# 7seg_unit_smd.net
KiCad netlist of a schematic drawn in EAGLE
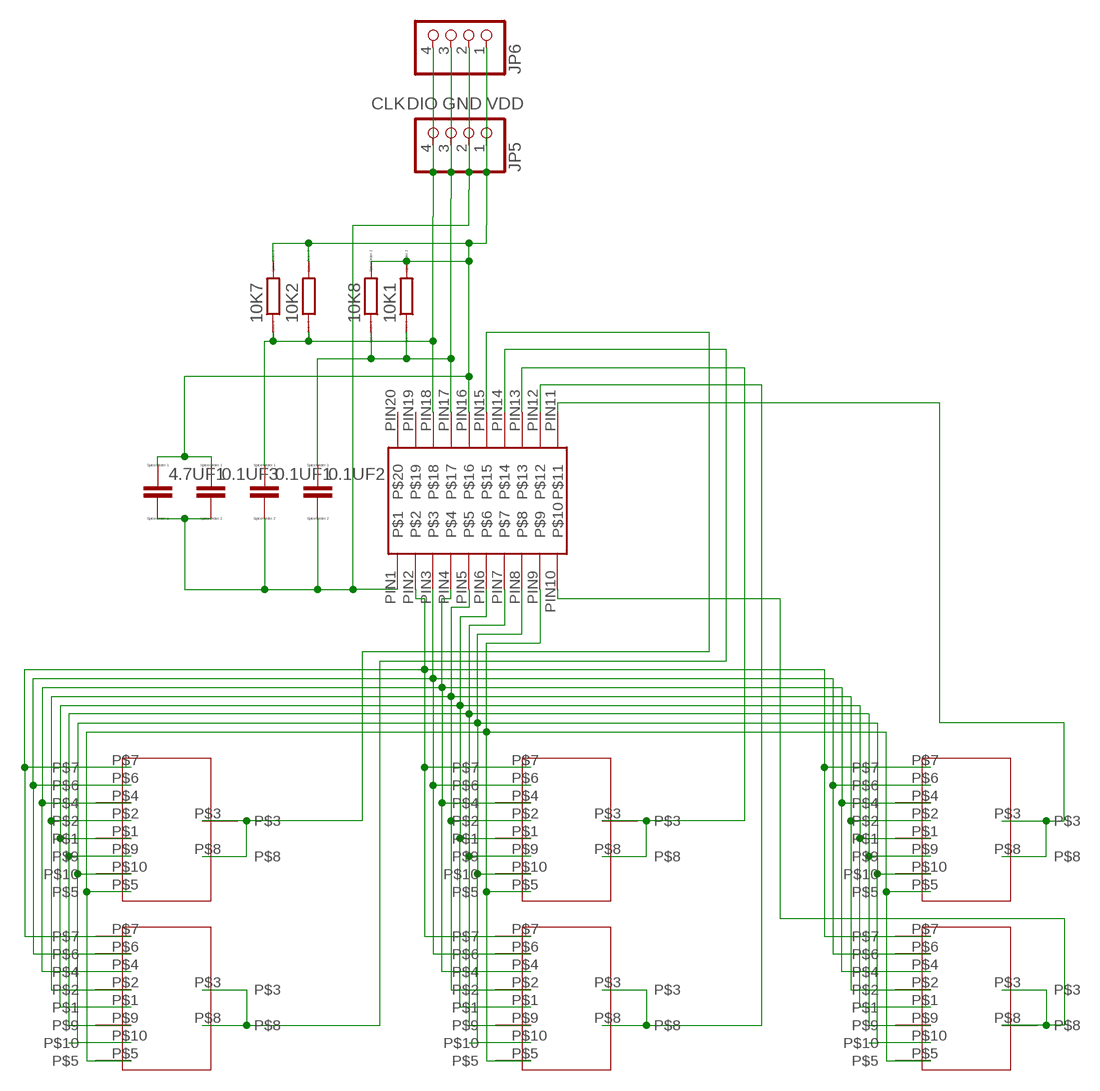
[diagram p0: schematic, sheet 1]

(export (version "E")
  (design (tool "Eeschema 10.0.6"))
  (components
    (comp (ref "0.1UF1")
      (value "CC1206")
      (footprint "eagle-import:C1206")
      (libsource (lib "eagle-import") (part "CC1206"))
    )
    (comp (ref "0.1UF2")
      (value "CC1206")
      (footprint "eagle-import:C1206")
      (libsource (lib "eagle-import") (part "CC1206"))
    )
    (comp (ref "0.1UF3")
      (value "CC1206")
      (footprint "eagle-import:C1206")
      (libsource (lib "eagle-import") (part "CC1206"))
    )
    (comp (ref "4.7UF1")
      (value "CC2012")
      (footprint "eagle-import:C2012")
      (libsource (lib "eagle-import") (part "CC2012"))
    )
    (comp (ref "7SEG_NEW1")
      (value "7SEG_NEW")
      (footprint "eagle-import:7SEG_NEW")
      (libsource (lib "eagle-import") (part "7SEG_NEW"))
    )
    (comp (ref "7SEG_NEW2")
      (value "7SEG_NEW")
      (footprint "eagle-import:7SEG_NEW")
      (libsource (lib "eagle-import") (part "7SEG_NEW"))
    )
    (comp (ref "7SEG_NEW3")
      (value "7SEG_NEW")
      (footprint "eagle-import:7SEG_NEW")
      (libsource (lib "eagle-import") (part "7SEG_NEW"))
    )
    (comp (ref "7SEG_NEW4")
      (value "7SEG_NEW")
      (footprint "eagle-import:7SEG_NEW")
      (libsource (lib "eagle-import") (part "7SEG_NEW"))
    )
    (comp (ref "7SEG_NEW5")
      (value "7SEG_NEW")
      (footprint "eagle-import:7SEG_NEW")
      (libsource (lib "eagle-import") (part "7SEG_NEW"))
    )
    (comp (ref "7SEG_NEW6")
      (value "7SEG_NEW")
      (footprint "eagle-import:7SEG_NEW")
      (libsource (lib "eagle-import") (part "7SEG_NEW"))
    )
    (comp (ref "10K1")
      (value "RR1206")
      (footprint "eagle-import:R1206")
      (libsource (lib "eagle-import") (part "RR1206"))
    )
    (comp (ref "10K2")
      (value "RR1206")
      (footprint "eagle-import:R1206")
      (libsource (lib "eagle-import") (part "RR1206"))
    )
    (comp (ref "10K7")
      (value "RR1206")
      (footprint "eagle-import:R1206")
      (libsource (lib "eagle-import") (part "RR1206"))
    )
    (comp (ref "10K8")
      (value "RR1206")
      (footprint "eagle-import:R1206")
      (libsource (lib "eagle-import") (part "RR1206"))
    )
    (comp (ref "JP5")
      (value "PINHD-1X4")
      (footprint "eagle-import:1X04")
      (libsource (lib "eagle-import") (part "PINHD-1X4"))
    )
    (comp (ref "JP6")
      (value "PINHD-1X4")
      (footprint "eagle-import:1X04")
      (libsource (lib "eagle-import") (part "PINHD-1X4"))
    )
    (comp (ref "TM1637-SMD1")
      (value "TM1637")
      (footprint "eagle-import:TM1637")
      (libsource (lib "eagle-import") (part "TM1637"))
    )
  )
  (nets
    (net (code "1") (name "/CLK") (class "Default")
      (node (ref "0.1UF1") (pin "1") (pinfunction "1_1") (pintype "passive"))
      (node (ref "10K2") (pin "1") (pinfunction "1_1") (pintype "passive"))
      (node (ref "10K7") (pin "1") (pinfunction "1_1") (pintype "passive"))
      (node (ref "JP5") (pin "4") (pinfunction "4_4") (pintype "passive"))
      (node (ref "JP6") (pin "4") (pinfunction "4_4") (pintype "passive"))
      (node (ref "TM1637-SMD1") (pin "PIN18") (pinfunction "P$18_PIN18") (pintype "bidirectional"))
    )
    (net (code "2") (name "/DIO") (class "Default")
      (node (ref "0.1UF2") (pin "1") (pinfunction "1_1") (pintype "passive"))
      (node (ref "10K1") (pin "1") (pinfunction "1_1") (pintype "passive"))
      (node (ref "10K8") (pin "1") (pinfunction "1_1") (pintype "passive"))
      (node (ref "JP5") (pin "3") (pinfunction "3_3") (pintype "passive"))
      (node (ref "JP6") (pin "3") (pinfunction "3_3") (pintype "passive"))
      (node (ref "TM1637-SMD1") (pin "PIN17") (pinfunction "P$17_PIN17") (pintype "bidirectional"))
    )
    (net (code "3") (name "/GND") (class "Default")
      (node (ref "0.1UF1") (pin "2") (pinfunction "2_2") (pintype "passive"))
      (node (ref "0.1UF2") (pin "2") (pinfunction "2_2") (pintype "passive"))
      (node (ref "0.1UF3") (pin "2") (pinfunction "2_2") (pintype "passive"))
      (node (ref "4.7UF1") (pin "2") (pinfunction "2_2") (pintype "passive"))
      (node (ref "JP5") (pin "2") (pinfunction "2_2") (pintype "passive"))
      (node (ref "JP6") (pin "2") (pinfunction "2_2") (pintype "passive"))
      (node (ref "TM1637-SMD1") (pin "PIN1") (pinfunction "P$1_PIN1") (pintype "bidirectional"))
    )
    (net (code "4") (name "/VDD") (class "Default")
      (node (ref "0.1UF3") (pin "1") (pinfunction "1_1") (pintype "passive"))
      (node (ref "10K1") (pin "2") (pinfunction "2_2") (pintype "passive"))
      (node (ref "10K2") (pin "2") (pinfunction "2_2") (pintype "passive"))
      (node (ref "10K7") (pin "2") (pinfunction "2_2") (pintype "passive"))
      (node (ref "10K8") (pin "2") (pinfunction "2_2") (pintype "passive"))
      (node (ref "4.7UF1") (pin "1") (pinfunction "1_1") (pintype "passive"))
      (node (ref "JP5") (pin "1") (pinfunction "1_1") (pintype "passive"))
      (node (ref "JP6") (pin "1") (pinfunction "1_1") (pintype "passive"))
      (node (ref "TM1637-SMD1") (pin "PIN16") (pinfunction "P$16_PIN16") (pintype "bidirectional"))
    )
    (net (code "5") (name "Net-(TM1637-SMD1-P$2)") (class "Default")
      (node (ref "7SEG_NEW1") (pin "P$7") (pinfunction "P$7_P$7") (pintype "bidirectional"))
      (node (ref "7SEG_NEW2") (pin "P$7") (pinfunction "P$7_P$7") (pintype "bidirectional"))
      (node (ref "7SEG_NEW3") (pin "P$7") (pinfunction "P$7_P$7") (pintype "bidirectional"))
      (node (ref "7SEG_NEW4") (pin "P$7") (pinfunction "P$7_P$7") (pintype "bidirectional"))
      (node (ref "7SEG_NEW5") (pin "P$7") (pinfunction "P$7_P$7") (pintype "bidirectional"))
      (node (ref "7SEG_NEW6") (pin "P$7") (pinfunction "P$7_P$7") (pintype "bidirectional"))
      (node (ref "TM1637-SMD1") (pin "PIN2") (pinfunction "P$2_PIN2") (pintype "bidirectional"))
    )
    (net (code "6") (name "Net-(TM1637-SMD1-P$3)") (class "Default")
      (node (ref "7SEG_NEW1") (pin "P$6") (pinfunction "P$6_P$6") (pintype "bidirectional"))
      (node (ref "7SEG_NEW2") (pin "P$6") (pinfunction "P$6_P$6") (pintype "bidirectional"))
      (node (ref "7SEG_NEW3") (pin "P$6") (pinfunction "P$6_P$6") (pintype "bidirectional"))
      (node (ref "7SEG_NEW4") (pin "P$6") (pinfunction "P$6_P$6") (pintype "bidirectional"))
      (node (ref "7SEG_NEW5") (pin "P$6") (pinfunction "P$6_P$6") (pintype "bidirectional"))
      (node (ref "7SEG_NEW6") (pin "P$6") (pinfunction "P$6_P$6") (pintype "bidirectional"))
      (node (ref "TM1637-SMD1") (pin "PIN3") (pinfunction "P$3_PIN3") (pintype "bidirectional"))
    )
    (net (code "7") (name "Net-(TM1637-SMD1-P$4)") (class "Default")
      (node (ref "7SEG_NEW1") (pin "P$4") (pinfunction "P$4_P$4") (pintype "bidirectional"))
      (node (ref "7SEG_NEW2") (pin "P$4") (pinfunction "P$4_P$4") (pintype "bidirectional"))
      (node (ref "7SEG_NEW3") (pin "P$4") (pinfunction "P$4_P$4") (pintype "bidirectional"))
      (node (ref "7SEG_NEW4") (pin "P$4") (pinfunction "P$4_P$4") (pintype "bidirectional"))
      (node (ref "7SEG_NEW5") (pin "P$4") (pinfunction "P$4_P$4") (pintype "bidirectional"))
      (node (ref "7SEG_NEW6") (pin "P$4") (pinfunction "P$4_P$4") (pintype "bidirectional"))
      (node (ref "TM1637-SMD1") (pin "PIN4") (pinfunction "P$4_PIN4") (pintype "bidirectional"))
    )
    (net (code "8") (name "Net-(TM1637-SMD1-P$5)") (class "Default")
      (node (ref "7SEG_NEW1") (pin "P$2") (pinfunction "P$2_P$2") (pintype "bidirectional"))
      (node (ref "7SEG_NEW2") (pin "P$2") (pinfunction "P$2_P$2") (pintype "bidirectional"))
      (node (ref "7SEG_NEW3") (pin "P$2") (pinfunction "P$2_P$2") (pintype "bidirectional"))
      (node (ref "7SEG_NEW4") (pin "P$2") (pinfunction "P$2_P$2") (pintype "bidirectional"))
      (node (ref "7SEG_NEW5") (pin "P$2") (pinfunction "P$2_P$2") (pintype "bidirectional"))
      (node (ref "7SEG_NEW6") (pin "P$2") (pinfunction "P$2_P$2") (pintype "bidirectional"))
      (node (ref "TM1637-SMD1") (pin "PIN5") (pinfunction "P$5_PIN5") (pintype "bidirectional"))
    )
    (net (code "9") (name "Net-(TM1637-SMD1-P$6)") (class "Default")
      (node (ref "7SEG_NEW1") (pin "P$1") (pinfunction "P$1_P$1") (pintype "bidirectional"))
      (node (ref "7SEG_NEW2") (pin "P$1") (pinfunction "P$1_P$1") (pintype "bidirectional"))
      (node (ref "7SEG_NEW3") (pin "P$1") (pinfunction "P$1_P$1") (pintype "bidirectional"))
      (node (ref "7SEG_NEW4") (pin "P$1") (pinfunction "P$1_P$1") (pintype "bidirectional"))
      (node (ref "7SEG_NEW5") (pin "P$1") (pinfunction "P$1_P$1") (pintype "bidirectional"))
      (node (ref "7SEG_NEW6") (pin "P$1") (pinfunction "P$1_P$1") (pintype "bidirectional"))
      (node (ref "TM1637-SMD1") (pin "PIN6") (pinfunction "P$6_PIN6") (pintype "bidirectional"))
    )
    (net (code "10") (name "Net-(TM1637-SMD1-P$7)") (class "Default")
      (node (ref "7SEG_NEW1") (pin "P$9") (pinfunction "P$9_P$9") (pintype "bidirectional"))
      (node (ref "7SEG_NEW2") (pin "P$9") (pinfunction "P$9_P$9") (pintype "bidirectional"))
      (node (ref "7SEG_NEW3") (pin "P$9") (pinfunction "P$9_P$9") (pintype "bidirectional"))
      (node (ref "7SEG_NEW4") (pin "P$9") (pinfunction "P$9_P$9") (pintype "bidirectional"))
      (node (ref "7SEG_NEW5") (pin "P$9") (pinfunction "P$9_P$9") (pintype "bidirectional"))
      (node (ref "7SEG_NEW6") (pin "P$9") (pinfunction "P$9_P$9") (pintype "bidirectional"))
      (node (ref "TM1637-SMD1") (pin "PIN7") (pinfunction "P$7_PIN7") (pintype "bidirectional"))
    )
    (net (code "11") (name "Net-(TM1637-SMD1-P$8)") (class "Default")
      (node (ref "7SEG_NEW1") (pin "P$10") (pinfunction "P$10_P$10") (pintype "bidirectional"))
      (node (ref "7SEG_NEW2") (pin "P$10") (pinfunction "P$10_P$10") (pintype "bidirectional"))
      (node (ref "7SEG_NEW3") (pin "P$10") (pinfunction "P$10_P$10") (pintype "bidirectional"))
      (node (ref "7SEG_NEW4") (pin "P$10") (pinfunction "P$10_P$10") (pintype "bidirectional"))
      (node (ref "7SEG_NEW5") (pin "P$10") (pinfunction "P$10_P$10") (pintype "bidirectional"))
      (node (ref "7SEG_NEW6") (pin "P$10") (pinfunction "P$10_P$10") (pintype "bidirectional"))
      (node (ref "TM1637-SMD1") (pin "PIN8") (pinfunction "P$8_PIN8") (pintype "bidirectional"))
    )
    (net (code "12") (name "Net-(TM1637-SMD1-P$9)") (class "Default")
      (node (ref "7SEG_NEW1") (pin "P$5") (pinfunction "P$5_P$5") (pintype "bidirectional"))
      (node (ref "7SEG_NEW2") (pin "P$5") (pinfunction "P$5_P$5") (pintype "bidirectional"))
      (node (ref "7SEG_NEW3") (pin "P$5") (pinfunction "P$5_P$5") (pintype "bidirectional"))
      (node (ref "7SEG_NEW4") (pin "P$5") (pinfunction "P$5_P$5") (pintype "bidirectional"))
      (node (ref "7SEG_NEW5") (pin "P$5") (pinfunction "P$5_P$5") (pintype "bidirectional"))
      (node (ref "7SEG_NEW6") (pin "P$5") (pinfunction "P$5_P$5") (pintype "bidirectional"))
      (node (ref "TM1637-SMD1") (pin "PIN9") (pinfunction "P$9_PIN9") (pintype "bidirectional"))
    )
    (net (code "13") (name "Net-(TM1637-SMD1-P$10)") (class "Default")
      (node (ref "7SEG_NEW6") (pin "P$3") (pinfunction "P$3_P$3") (pintype "bidirectional"))
      (node (ref "7SEG_NEW6") (pin "P$8") (pinfunction "P$8_P$8") (pintype "bidirectional"))
      (node (ref "TM1637-SMD1") (pin "PIN10") (pinfunction "P$10_PIN10") (pintype "bidirectional"))
    )
    (net (code "14") (name "Net-(TM1637-SMD1-P$11)") (class "Default")
      (node (ref "7SEG_NEW5") (pin "P$3") (pinfunction "P$3_P$3") (pintype "bidirectional"))
      (node (ref "7SEG_NEW5") (pin "P$8") (pinfunction "P$8_P$8") (pintype "bidirectional"))
      (node (ref "TM1637-SMD1") (pin "PIN11") (pinfunction "P$11_PIN11") (pintype "bidirectional"))
    )
    (net (code "15") (name "Net-(TM1637-SMD1-P$12)") (class "Default")
      (node (ref "7SEG_NEW2") (pin "P$3") (pinfunction "P$3_P$3") (pintype "bidirectional"))
      (node (ref "7SEG_NEW2") (pin "P$8") (pinfunction "P$8_P$8") (pintype "bidirectional"))
      (node (ref "TM1637-SMD1") (pin "PIN12") (pinfunction "P$12_PIN12") (pintype "bidirectional"))
    )
    (net (code "16") (name "Net-(TM1637-SMD1-P$13)") (class "Default")
      (node (ref "7SEG_NEW1") (pin "P$3") (pinfunction "P$3_P$3") (pintype "bidirectional"))
      (node (ref "7SEG_NEW1") (pin "P$8") (pinfunction "P$8_P$8") (pintype "bidirectional"))
      (node (ref "TM1637-SMD1") (pin "PIN13") (pinfunction "P$13_PIN13") (pintype "bidirectional"))
    )
    (net (code "17") (name "Net-(TM1637-SMD1-P$14)") (class "Default")
      (node (ref "7SEG_NEW4") (pin "P$3") (pinfunction "P$3_P$3") (pintype "bidirectional"))
      (node (ref "7SEG_NEW4") (pin "P$8") (pinfunction "P$8_P$8") (pintype "bidirectional"))
      (node (ref "TM1637-SMD1") (pin "PIN14") (pinfunction "P$14_PIN14") (pintype "bidirectional"))
    )
    (net (code "18") (name "Net-(TM1637-SMD1-P$15)") (class "Default")
      (node (ref "7SEG_NEW3") (pin "P$3") (pinfunction "P$3_P$3") (pintype "bidirectional"))
      (node (ref "7SEG_NEW3") (pin "P$8") (pinfunction "P$8_P$8") (pintype "bidirectional"))
      (node (ref "TM1637-SMD1") (pin "PIN15") (pinfunction "P$15_PIN15") (pintype "bidirectional"))
    )
    (net (code "19") (name "unconnected-(TM1637-SMD1-P$19-PadPIN19)") (class "Default")
      (node (ref "TM1637-SMD1") (pin "PIN19") (pinfunction "P$19_PIN19") (pintype "bidirectional"))
    )
    (net (code "20") (name "unconnected-(TM1637-SMD1-P$20-PadPIN20)") (class "Default")
      (node (ref "TM1637-SMD1") (pin "PIN20") (pinfunction "P$20_PIN20") (pintype "bidirectional"))
    )
  )
)
